# board.net
KiCad netlist of a schematic drawn in EAGLE
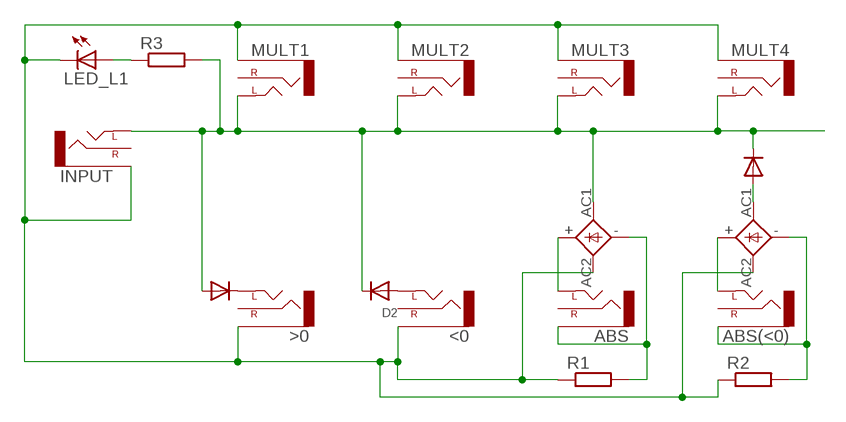
[diagram p0: schematic, sheet 1]

(export (version "E")
  (design (tool "Eeschema 10.0.6"))
  (components
    (comp (ref "<0")
      (value "THONKI-STEREO")
      (footprint "eagle-import:WQP-PJ366ST_JACK")
      (libsource (lib "eagle-import") (part "THONKI-STEREO"))
    )
    (comp (ref ">0")
      (value "THONKI-STEREO")
      (footprint "eagle-import:WQP-PJ366ST_JACK")
      (libsource (lib "eagle-import") (part "THONKI-STEREO"))
    )
    (comp (ref "ABS")
      (value "THONKI-STEREO")
      (footprint "eagle-import:WQP-PJ366ST_JACK")
      (libsource (lib "eagle-import") (part "THONKI-STEREO"))
    )
    (comp (ref "ABS(<0)")
      (value "THONKI-STEREO")
      (footprint "eagle-import:WQP-PJ366ST_JACK")
      (libsource (lib "eagle-import") (part "THONKI-STEREO"))
    )
    (comp (ref "B1")
      (value "2KBB-R")
      (footprint "eagle-import:2KBB-R")
      (libsource (lib "eagle-import") (part "2KBB-R"))
    )
    (comp (ref "B2")
      (value "2KBB-R")
      (footprint "eagle-import:2KBB-R")
      (libsource (lib "eagle-import") (part "2KBB-R"))
    )
    (comp (ref "D1")
      (value "DIODEDO-1N4148")
      (footprint "eagle-import:DO-1N4148")
      (libsource (lib "eagle-import") (part "DIODEDO-1N4148"))
    )
    (comp (ref "D2")
      (value "DIODEDO-1N4148")
      (footprint "eagle-import:DO-1N4148")
      (libsource (lib "eagle-import") (part "DIODEDO-1N4148"))
    )
    (comp (ref "D3")
      (value "DIODEDO-1N4148")
      (footprint "eagle-import:DO-1N4148")
      (libsource (lib "eagle-import") (part "DIODEDO-1N4148"))
    )
    (comp (ref "INPUT")
      (value "THONKI-STEREO")
      (footprint "eagle-import:WQP-PJ366ST_JACK")
      (libsource (lib "eagle-import") (part "THONKI-STEREO"))
    )
    (comp (ref "LED_L1")
      (value "LED3MM")
      (footprint "eagle-import:LED3MM")
      (libsource (lib "eagle-import") (part "LED3MM"))
    )
    (comp (ref "MULT1")
      (value "THONKI-STEREO")
      (footprint "eagle-import:WQP-PJ366ST_JACK")
      (libsource (lib "eagle-import") (part "THONKI-STEREO"))
    )
    (comp (ref "MULT2")
      (value "THONKI-STEREO")
      (footprint "eagle-import:WQP-PJ366ST_JACK")
      (libsource (lib "eagle-import") (part "THONKI-STEREO"))
    )
    (comp (ref "MULT3")
      (value "THONKI-STEREO")
      (footprint "eagle-import:WQP-PJ366ST_JACK")
      (libsource (lib "eagle-import") (part "THONKI-STEREO"))
    )
    (comp (ref "MULT4")
      (value "THONKI-STEREO")
      (footprint "eagle-import:WQP-PJ366ST_JACK")
      (libsource (lib "eagle-import") (part "THONKI-STEREO"))
    )
    (comp (ref "R1")
      (value "RESISTOR7MM")
      (footprint "eagle-import:7MM_RESISTOR")
      (libsource (lib "eagle-import") (part "RESISTOR7MM"))
    )
    (comp (ref "R2")
      (value "RESISTOR7MM")
      (footprint "eagle-import:7MM_RESISTOR")
      (libsource (lib "eagle-import") (part "RESISTOR7MM"))
    )
    (comp (ref "R3")
      (value "RESISTOR7MM")
      (footprint "eagle-import:7MM_RESISTOR")
      (libsource (lib "eagle-import") (part "RESISTOR7MM"))
    )
  )
  (nets
    (net (code "1") (name "Net-(<0-LEFT)") (class "Default")
      (node (ref "<0") (pin "P$1_TIP") (pinfunction "LEFT_P$1_TIP") (pintype "bidirectional"))
      (node (ref "D2") (pin "A") (pinfunction "A_A") (pintype "passive"))
    )
    (net (code "2") (name "Net-(<0-SLEEVE)") (class "Default")
      (node (ref "<0") (pin "P$3_SLEEVE") (pinfunction "SLEEVE_P$3_SLEEVE") (pintype "bidirectional"))
      (node (ref ">0") (pin "P$3_SLEEVE") (pinfunction "SLEEVE_P$3_SLEEVE") (pintype "bidirectional"))
      (node (ref "B1") (pin "AC2") (pinfunction "AC2_AC2") (pintype "passive"))
      (node (ref "B2") (pin "AC2") (pinfunction "AC2_AC2") (pintype "passive"))
      (node (ref "INPUT") (pin "P$3_SLEEVE") (pinfunction "SLEEVE_P$3_SLEEVE") (pintype "bidirectional"))
      (node (ref "LED_L1") (pin "K") (pinfunction "C_K") (pintype "passive"))
      (node (ref "MULT1") (pin "P$3_SLEEVE") (pinfunction "SLEEVE_P$3_SLEEVE") (pintype "bidirectional"))
      (node (ref "MULT2") (pin "P$3_SLEEVE") (pinfunction "SLEEVE_P$3_SLEEVE") (pintype "bidirectional"))
      (node (ref "MULT3") (pin "P$3_SLEEVE") (pinfunction "SLEEVE_P$3_SLEEVE") (pintype "bidirectional"))
      (node (ref "MULT4") (pin "P$3_SLEEVE") (pinfunction "SLEEVE_P$3_SLEEVE") (pintype "bidirectional"))
      (node (ref "R1") (pin "1") (pinfunction "1_1") (pintype "passive"))
      (node (ref "R2") (pin "1") (pinfunction "1_1") (pintype "passive"))
    )
    (net (code "3") (name "Net-(>0-LEFT)") (class "Default")
      (node (ref ">0") (pin "P$1_TIP") (pinfunction "LEFT_P$1_TIP") (pintype "bidirectional"))
      (node (ref "D1") (pin "C") (pinfunction "C_C") (pintype "passive"))
    )
    (net (code "4") (name "Net-(ABS(<0)-LEFT)") (class "Default")
      (node (ref "ABS(<0)") (pin "P$1_TIP") (pinfunction "LEFT_P$1_TIP") (pintype "bidirectional"))
      (node (ref "B2") (pin "+") (pinfunction "+_+") (pintype "passive"))
    )
    (net (code "5") (name "Net-(ABS(<0)-SLEEVE)") (class "Default")
      (node (ref "ABS(<0)") (pin "P$3_SLEEVE") (pinfunction "SLEEVE_P$3_SLEEVE") (pintype "bidirectional"))
      (node (ref "B2") (pin "-") (pinfunction "-_-") (pintype "passive"))
      (node (ref "R2") (pin "2") (pinfunction "2_2") (pintype "passive"))
    )
    (net (code "6") (name "Net-(ABS-LEFT)") (class "Default")
      (node (ref "ABS") (pin "P$1_TIP") (pinfunction "LEFT_P$1_TIP") (pintype "bidirectional"))
      (node (ref "B1") (pin "+") (pinfunction "+_+") (pintype "passive"))
    )
    (net (code "7") (name "Net-(ABS-SLEEVE)") (class "Default")
      (node (ref "ABS") (pin "P$3_SLEEVE") (pinfunction "SLEEVE_P$3_SLEEVE") (pintype "bidirectional"))
      (node (ref "B1") (pin "-") (pinfunction "-_-") (pintype "passive"))
      (node (ref "R1") (pin "2") (pinfunction "2_2") (pintype "passive"))
    )
    (net (code "8") (name "Net-(B2-PadAC1)") (class "Default")
      (node (ref "B2") (pin "AC1") (pinfunction "AC1_AC1") (pintype "passive"))
      (node (ref "D3") (pin "A") (pinfunction "A_A") (pintype "passive"))
    )
    (net (code "9") (name "Net-(INPUT-LEFT)") (class "Default")
      (node (ref "B1") (pin "AC1") (pinfunction "AC1_AC1") (pintype "passive"))
      (node (ref "D1") (pin "A") (pinfunction "A_A") (pintype "passive"))
      (node (ref "D2") (pin "C") (pinfunction "C_C") (pintype "passive"))
      (node (ref "D3") (pin "C") (pinfunction "C_C") (pintype "passive"))
      (node (ref "INPUT") (pin "P$1_TIP") (pinfunction "LEFT_P$1_TIP") (pintype "bidirectional"))
      (node (ref "MULT1") (pin "P$1_TIP") (pinfunction "LEFT_P$1_TIP") (pintype "bidirectional"))
      (node (ref "MULT2") (pin "P$1_TIP") (pinfunction "LEFT_P$1_TIP") (pintype "bidirectional"))
      (node (ref "MULT3") (pin "P$1_TIP") (pinfunction "LEFT_P$1_TIP") (pintype "bidirectional"))
      (node (ref "MULT4") (pin "P$1_TIP") (pinfunction "LEFT_P$1_TIP") (pintype "bidirectional"))
      (node (ref "R3") (pin "2") (pinfunction "2_2") (pintype "passive"))
    )
    (net (code "10") (name "Net-(LED_L1-PadA)") (class "Default")
      (node (ref "LED_L1") (pin "A") (pinfunction "A_A") (pintype "passive"))
      (node (ref "R3") (pin "1") (pinfunction "1_1") (pintype "passive"))
    )
    (net (code "11") (name "unconnected-(<0-RIGHT-PadP$2_SWITCH)") (class "Default")
      (node (ref "<0") (pin "P$2_SWITCH") (pinfunction "RIGHT_P$2_SWITCH") (pintype "bidirectional"))
    )
    (net (code "12") (name "unconnected-(>0-RIGHT-PadP$2_SWITCH)") (class "Default")
      (node (ref ">0") (pin "P$2_SWITCH") (pinfunction "RIGHT_P$2_SWITCH") (pintype "bidirectional"))
    )
    (net (code "13") (name "unconnected-(ABS(<0)-RIGHT-PadP$2_SWITCH)") (class "Default")
      (node (ref "ABS(<0)") (pin "P$2_SWITCH") (pinfunction "RIGHT_P$2_SWITCH") (pintype "bidirectional"))
    )
    (net (code "14") (name "unconnected-(ABS-RIGHT-PadP$2_SWITCH)") (class "Default")
      (node (ref "ABS") (pin "P$2_SWITCH") (pinfunction "RIGHT_P$2_SWITCH") (pintype "bidirectional"))
    )
    (net (code "15") (name "unconnected-(INPUT-RIGHT-PadP$2_SWITCH)") (class "Default")
      (node (ref "INPUT") (pin "P$2_SWITCH") (pinfunction "RIGHT_P$2_SWITCH") (pintype "bidirectional"))
    )
    (net (code "16") (name "unconnected-(MULT1-RIGHT-PadP$2_SWITCH)") (class "Default")
      (node (ref "MULT1") (pin "P$2_SWITCH") (pinfunction "RIGHT_P$2_SWITCH") (pintype "bidirectional"))
    )
    (net (code "17") (name "unconnected-(MULT2-RIGHT-PadP$2_SWITCH)") (class "Default")
      (node (ref "MULT2") (pin "P$2_SWITCH") (pinfunction "RIGHT_P$2_SWITCH") (pintype "bidirectional"))
    )
    (net (code "18") (name "unconnected-(MULT3-RIGHT-PadP$2_SWITCH)") (class "Default")
      (node (ref "MULT3") (pin "P$2_SWITCH") (pinfunction "RIGHT_P$2_SWITCH") (pintype "bidirectional"))
    )
    (net (code "19") (name "unconnected-(MULT4-RIGHT-PadP$2_SWITCH)") (class "Default")
      (node (ref "MULT4") (pin "P$2_SWITCH") (pinfunction "RIGHT_P$2_SWITCH") (pintype "bidirectional"))
    )
  )
)
